# 13_-BACKUP_POWER.net
KiCad netlist of a schematic drawn in Altium Designer
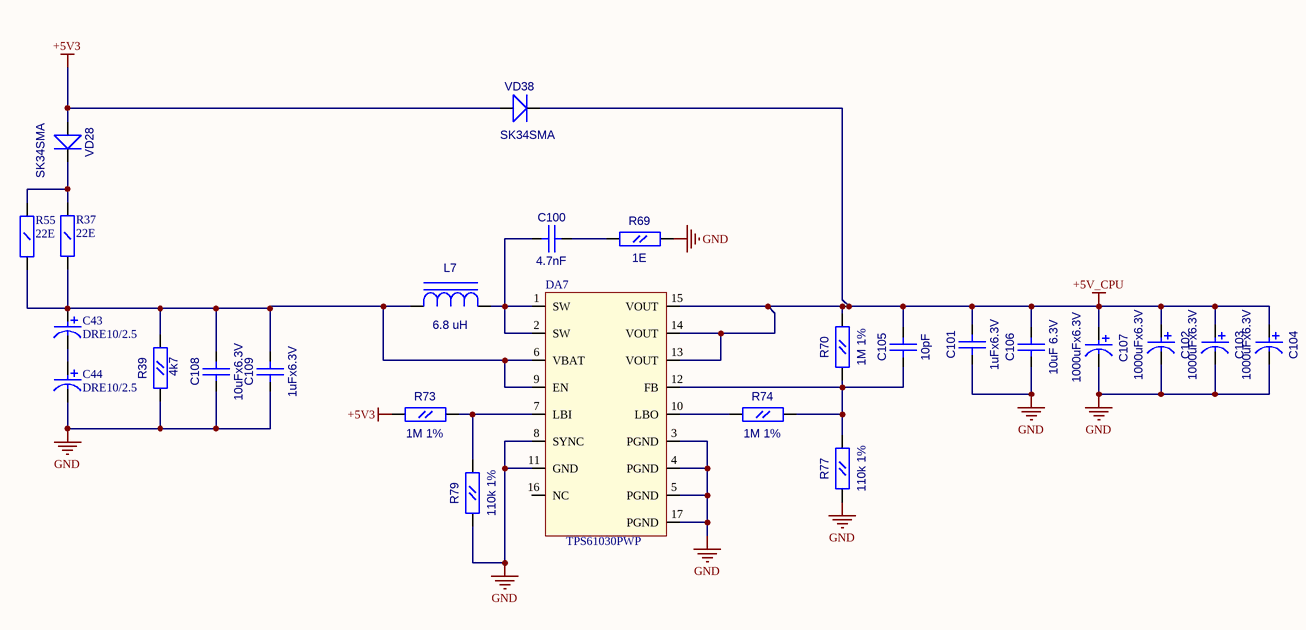
[diagram p0: [13]-BACKUP_POWER.SchDoc]

(export (version "E")
  (design (tool "Eeschema 10.0.6"))
  (components
    (comp (ref "C43")
      (value "DRE10/2.5")
      (footprint "CAP16_26")
      (libsource (lib "fizik_lib (1)") (part "SUPERCAP_10F"))
    )
    (comp (ref "C44")
      (value "DRE10/2.5")
      (footprint "CAP16_26")
      (libsource (lib "fizik_lib (1)") (part "SUPERCAP_10F"))
    )
    (comp (ref "C100")
      (value "4.7nF")
      (footprint "CC0603")
      (description "CC0603")
      (libsource (lib "gprs_modem_2") (part "CC0603"))
    )
    (comp (ref "C101")
      (value "1uFx6.3V")
      (footprint "CC0603")
      (description "CC0603")
      (libsource (lib "fizik_lib (1)") (part "CC0603"))
    )
    (comp (ref "C102")
      (value "1000uFx6.3V")
      (footprint "CC8X3.5")
      (description "CAP0.35")
      (libsource (lib "gprs_modem_2") (part "CAP0.35"))
    )
    (comp (ref "C103")
      (value "1000uFx6.3V")
      (footprint "CC8X3.5")
      (description "CAP0.35")
      (libsource (lib "gprs_modem_2") (part "CAP0.35"))
    )
    (comp (ref "C104")
      (value "1000uFx6.3V")
      (footprint "CC8X3.5")
      (description "CAP0.35")
      (libsource (lib "gprs_modem_2") (part "CAP0.35"))
    )
    (comp (ref "C105")
      (value "10pF")
      (footprint "CC0603")
      (description "CC0603")
      (libsource (lib "gprs_modem_2") (part "CC0603"))
    )
    (comp (ref "C106")
      (value "10uF 6.3V")
      (footprint "CC0805")
      (description "CC0805")
      (libsource (lib "gprs_modem_2") (part "CC0805"))
    )
    (comp (ref "C107")
      (value "1000uFx6.3V")
      (footprint "CC8X3.5")
      (description "CAP0.35")
      (libsource (lib "gprs_modem_2") (part "CAP0.35"))
    )
    (comp (ref "C108")
      (value "10uFx6.3V")
      (footprint "CC0805")
      (description "CC0805")
      (libsource (lib "gprs_modem_2") (part "CC0805"))
    )
    (comp (ref "C109")
      (value "1uFx6.3V")
      (footprint "CC0603")
      (description "CC0603")
      (libsource (lib "fizik_lib (1)") (part "CC0603"))
    )
    (comp (ref "DA7")
      (value "TPS61030PWP")
      (footprint "R-PDSO-G16")
      (description "Boost converter")
      (libsource (lib "gprs_modem") (part "TPS61030PWP"))
    )
    (comp (ref "L7")
      (value "6.8 uH")
      (footprint "SDR0805")
      (description "SDR0805")
      (libsource (lib "gprs_modem_2") (part "SDR0805"))
    )
    (comp (ref "R37")
      (value "22E")
      (footprint "R2512")
      (description "Resistor 2512 1W")
      (libsource (lib "fizik_lib") (part "RC2512"))
    )
    (comp (ref "R39")
      (value "4k7")
      (footprint "RC0603")
      (description "RC0603")
      (libsource (lib "fizik_lib") (part "RC0603"))
    )
    (comp (ref "R55")
      (value "22E")
      (footprint "R2512")
      (description "Resistor 2512 1W")
      (libsource (lib "fizik_lib") (part "RC2512"))
    )
    (comp (ref "R69")
      (value "1E")
      (footprint "RC0603")
      (description "RC0603")
      (libsource (lib "gprs_modem_2") (part "RC0603"))
    )
    (comp (ref "R70")
      (value "1M 1%")
      (footprint "RC0603")
      (description "RC0603")
      (libsource (lib "gprs_modem_2") (part "RC0603"))
    )
    (comp (ref "R73")
      (value "1M 1%")
      (footprint "RC0603")
      (description "RC0603")
      (libsource (lib "gprs_modem_2") (part "RC0603"))
    )
    (comp (ref "R74")
      (value "1M 1%")
      (footprint "RC0603")
      (description "RC0603")
      (libsource (lib "gprs_modem_2") (part "RC0603"))
    )
    (comp (ref "R77")
      (value "110k 1%")
      (footprint "RC0603")
      (description "RC0603")
      (libsource (lib "gprs_modem_2") (part "RC0603"))
    )
    (comp (ref "R79")
      (value "110k 1%")
      (footprint "RC0603")
      (description "RC0603")
      (libsource (lib "gprs_modem_2") (part "RC0603"))
    )
    (comp (ref "VD28")
      (value "SK34SMA")
      (footprint "SMA")
      (description "Schottky Rectifier")
      (libsource (lib "fizik_lib (1)") (part "SK34SMA"))
    )
    (comp (ref "VD38")
      (value "SK34SMA")
      (footprint "SMA")
      (description "Schottky Rectifier")
      (libsource (lib "fizik_lib (1)") (part "SK34SMA"))
    )
  )
  (nets
    (net (code "1") (name "+5V3") (class "Default")
      (node (ref "R73") (pin "1") (pinfunction "A_1") (pintype "passive"))
      (node (ref "VD28") (pin "1") (pinfunction "A_1") (pintype "passive"))
      (node (ref "VD38") (pin "1") (pinfunction "A_1") (pintype "passive"))
    )
    (net (code "2") (name "+5V_CPU") (class "Default")
      (node (ref "C101") (pin "2") (pinfunction "B_2") (pintype "passive"))
      (node (ref "C102") (pin "1") (pintype "passive"))
      (node (ref "C103") (pin "1") (pintype "passive"))
      (node (ref "C104") (pin "1") (pintype "passive"))
      (node (ref "C105") (pin "2") (pinfunction "B_2") (pintype "passive"))
      (node (ref "C106") (pin "2") (pinfunction "B_2") (pintype "passive"))
      (node (ref "C107") (pin "1") (pintype "passive"))
      (node (ref "DA7") (pin "13") (pinfunction "VOUT_13") (pintype "passive"))
      (node (ref "DA7") (pin "14") (pinfunction "VOUT_14") (pintype "passive"))
      (node (ref "DA7") (pin "15") (pinfunction "VOUT_15") (pintype "passive"))
      (node (ref "R70") (pin "2") (pinfunction "B_2") (pintype "passive"))
      (node (ref "VD38") (pin "2") (pinfunction "K_2") (pintype "passive"))
    )
    (net (code "3") (name "GND") (class "Default")
      (node (ref "C101") (pin "1") (pinfunction "A_1") (pintype "passive"))
      (node (ref "C102") (pin "2") (pintype "passive"))
      (node (ref "C103") (pin "2") (pintype "passive"))
      (node (ref "C104") (pin "2") (pintype "passive"))
      (node (ref "C106") (pin "1") (pinfunction "A_1") (pintype "passive"))
      (node (ref "C107") (pin "2") (pintype "passive"))
      (node (ref "C108") (pin "1") (pinfunction "A_1") (pintype "passive"))
      (node (ref "C109") (pin "1") (pinfunction "A_1") (pintype "passive"))
      (node (ref "C44") (pin "1") (pintype "passive"))
      (node (ref "DA7") (pin "11") (pinfunction "GND_11") (pintype "passive"))
      (node (ref "DA7") (pin "17") (pinfunction "PGND_17") (pintype "passive"))
      (node (ref "DA7") (pin "3") (pinfunction "PGND_3") (pintype "passive"))
      (node (ref "DA7") (pin "4") (pinfunction "PGND_4") (pintype "passive"))
      (node (ref "DA7") (pin "5") (pinfunction "PGND_5") (pintype "passive"))
      (node (ref "DA7") (pin "8") (pinfunction "SYNC_8") (pintype "passive"))
      (node (ref "R39") (pin "1") (pinfunction "A_1") (pintype "passive"))
      (node (ref "R69") (pin "2") (pinfunction "B_2") (pintype "passive"))
      (node (ref "R77") (pin "1") (pinfunction "A_1") (pintype "passive"))
      (node (ref "R79") (pin "1") (pinfunction "A_1") (pintype "passive"))
    )
    (net (code "4") (name "Net-(C43-Pad1)") (class "Default")
      (node (ref "C43") (pin "1") (pintype "passive"))
      (node (ref "C44") (pin "2") (pintype "passive"))
    )
    (net (code "5") (name "Net-(C100-A)") (class "Default")
      (node (ref "C100") (pin "1") (pinfunction "A_1") (pintype "passive"))
      (node (ref "DA7") (pin "1") (pinfunction "SW_1") (pintype "passive"))
      (node (ref "DA7") (pin "2") (pinfunction "SW_2") (pintype "passive"))
      (node (ref "L7") (pin "2") (pinfunction "A_2") (pintype "passive"))
    )
    (net (code "6") (name "Net-(C100-B)") (class "Default")
      (node (ref "C100") (pin "2") (pinfunction "B_2") (pintype "passive"))
      (node (ref "R69") (pin "1") (pinfunction "A_1") (pintype "passive"))
    )
    (net (code "7") (name "Net-(C105-A)") (class "Default")
      (node (ref "C105") (pin "1") (pinfunction "A_1") (pintype "passive"))
      (node (ref "DA7") (pin "12") (pinfunction "FB_12") (pintype "passive"))
      (node (ref "R70") (pin "1") (pinfunction "A_1") (pintype "passive"))
      (node (ref "R74") (pin "2") (pinfunction "B_2") (pintype "passive"))
      (node (ref "R77") (pin "2") (pinfunction "B_2") (pintype "passive"))
    )
    (net (code "8") (name "Net-(C108-B)") (class "Default")
      (node (ref "C108") (pin "2") (pinfunction "B_2") (pintype "passive"))
      (node (ref "C109") (pin "2") (pinfunction "B_2") (pintype "passive"))
      (node (ref "C43") (pin "2") (pintype "passive"))
      (node (ref "DA7") (pin "6") (pinfunction "VBAT_6") (pintype "passive"))
      (node (ref "DA7") (pin "9") (pinfunction "EN_9") (pintype "passive"))
      (node (ref "L7") (pin "1") (pinfunction "C_1") (pintype "passive"))
      (node (ref "R37") (pin "1") (pinfunction "A_1") (pintype "passive"))
      (node (ref "R39") (pin "2") (pinfunction "B_2") (pintype "passive"))
      (node (ref "R55") (pin "1") (pinfunction "A_1") (pintype "passive"))
    )
    (net (code "9") (name "Net-(DA7-LBI)") (class "Default")
      (node (ref "DA7") (pin "7") (pinfunction "LBI_7") (pintype "passive"))
      (node (ref "R73") (pin "2") (pinfunction "B_2") (pintype "passive"))
      (node (ref "R79") (pin "2") (pinfunction "B_2") (pintype "passive"))
    )
    (net (code "10") (name "Net-(DA7-LBO)") (class "Default")
      (node (ref "DA7") (pin "10") (pinfunction "LBO_10") (pintype "passive"))
      (node (ref "R74") (pin "1") (pinfunction "A_1") (pintype "passive"))
    )
    (net (code "11") (name "Net-(R37-B)") (class "Default")
      (node (ref "R37") (pin "2") (pinfunction "B_2") (pintype "passive"))
      (node (ref "R55") (pin "2") (pinfunction "B_2") (pintype "passive"))
      (node (ref "VD28") (pin "2") (pinfunction "K_2") (pintype "passive"))
    )
    (net (code "12") (name "unconnected-(DA7-NC-Pad16)") (class "Default")
      (node (ref "DA7") (pin "16") (pinfunction "NC_16") (pintype "passive"))
    )
  )
)
